# il-serbatoio.net
KiCad netlist of a schematic drawn in EAGLE
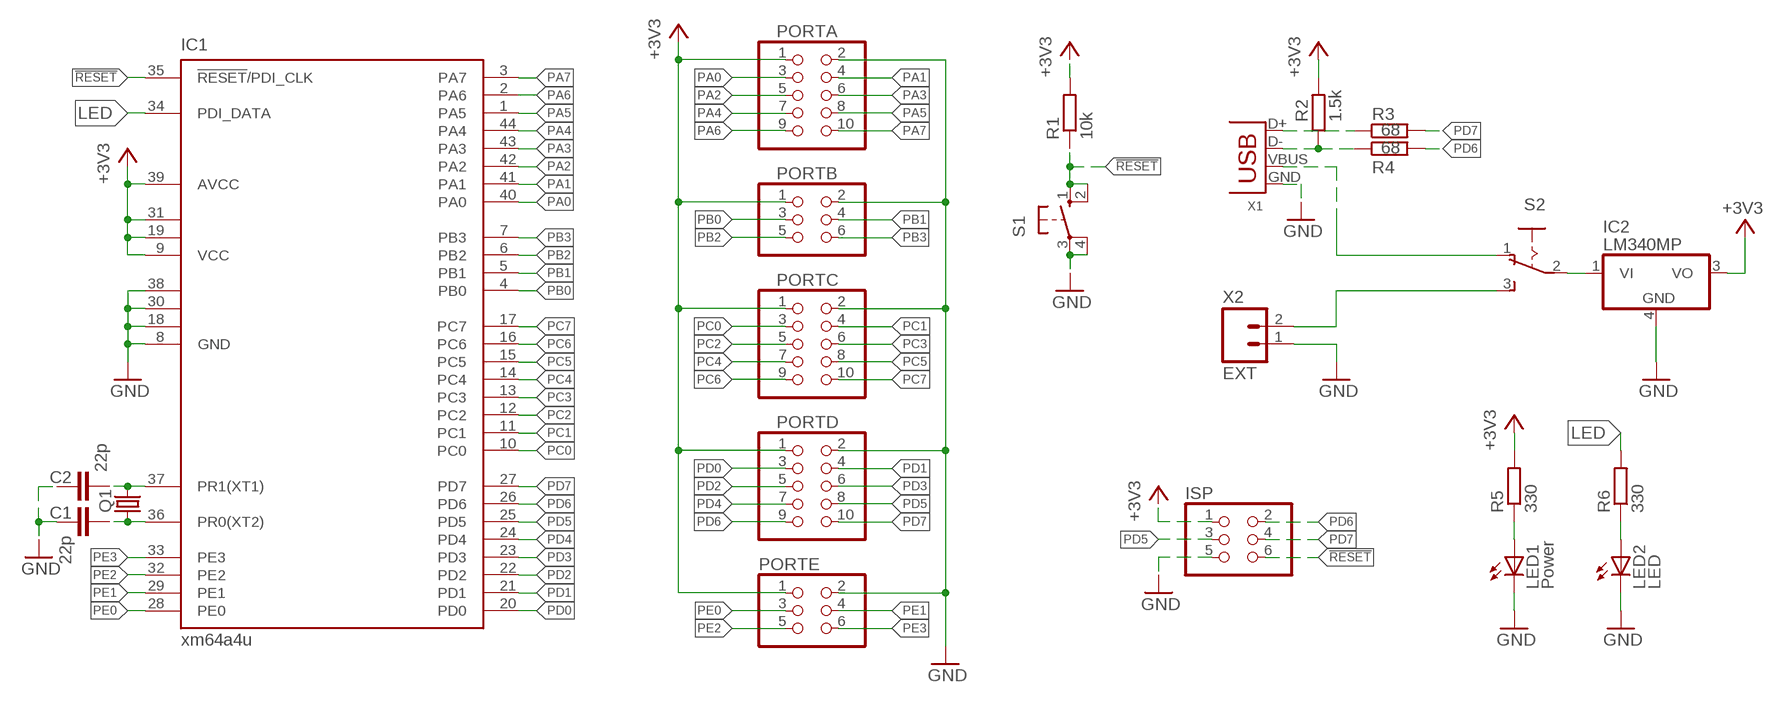
[diagram p0: schematic, sheet 1]

(export (version "E")
  (design (tool "Eeschema 10.0.6"))
  (components
    (comp (ref "C1")
      (value "22p")
      (footprint "eagle-import:C025-024X044")
      (libsource (lib "eagle-import") (part "C-EU025-024X044"))
    )
    (comp (ref "C2")
      (value "22p")
      (footprint "eagle-import:C025-024X044")
      (libsource (lib "eagle-import") (part "C-EU025-024X044"))
    )
    (comp (ref "IC1")
      (value "xm64a4u")
      (footprint "eagle-import:TQFP44")
      (libsource (lib "eagle-import") (part "XMEGA16A4A"))
    )
    (comp (ref "IC2")
      (value "LM340MP")
      (footprint "eagle-import:SOT223")
      (libsource (lib "eagle-import") (part "LM340?-MP05"))
    )
    (comp (ref "ISP")
      (value "PINHD-2X3")
      (footprint "eagle-import:2X03")
      (libsource (lib "eagle-import") (part "PINHD-2X3"))
    )
    (comp (ref "LED1")
      (value "Power")
      (footprint "eagle-import:CHIP-LED0805")
      (libsource (lib "eagle-import") (part "LEDCHIP-LED0805"))
    )
    (comp (ref "LED2")
      (value "LED")
      (footprint "eagle-import:CHIP-LED0805")
      (libsource (lib "eagle-import") (part "LEDCHIP-LED0805"))
    )
    (comp (ref "PORTA")
      (value "PINHD-2X5")
      (footprint "eagle-import:2X05")
      (libsource (lib "eagle-import") (part "PINHD-2X5"))
    )
    (comp (ref "PORTB")
      (value "PINHD-2X3")
      (footprint "eagle-import:2X03")
      (libsource (lib "eagle-import") (part "PINHD-2X3"))
    )
    (comp (ref "PORTC")
      (value "PINHD-2X5")
      (footprint "eagle-import:2X05")
      (libsource (lib "eagle-import") (part "PINHD-2X5"))
    )
    (comp (ref "PORTD")
      (value "PINHD-2X5")
      (footprint "eagle-import:2X05")
      (libsource (lib "eagle-import") (part "PINHD-2X5"))
    )
    (comp (ref "PORTE")
      (value "PINHD-2X3")
      (footprint "eagle-import:2X03")
      (libsource (lib "eagle-import") (part "PINHD-2X3"))
    )
    (comp (ref "Q1")
      (value "CRYSTALCTS406")
      (footprint "eagle-import:CTS406")
      (libsource (lib "eagle-import") (part "CRYSTALCTS406"))
    )
    (comp (ref "R1")
      (value "10k")
      (footprint "eagle-import:M0805")
      (libsource (lib "eagle-import") (part "R-EU_M0805"))
    )
    (comp (ref "R2")
      (value "1.5k")
      (footprint "eagle-import:M0805")
      (libsource (lib "eagle-import") (part "R-EU_M0805"))
    )
    (comp (ref "R3")
      (value "68")
      (footprint "eagle-import:M0805")
      (libsource (lib "eagle-import") (part "R-EU_M0805"))
    )
    (comp (ref "R4")
      (value "68")
      (footprint "eagle-import:M0805")
      (libsource (lib "eagle-import") (part "R-EU_M0805"))
    )
    (comp (ref "R5")
      (value "330")
      (footprint "eagle-import:M0805")
      (libsource (lib "eagle-import") (part "R-EU_M0805"))
    )
    (comp (ref "R6")
      (value "330")
      (footprint "eagle-import:M0805")
      (libsource (lib "eagle-import") (part "R-EU_M0805"))
    )
    (comp (ref "S1")
      (value "10-XX")
      (footprint "eagle-import:B3F-10XX")
      (fields (field (name "MPN") "B3F-1000"))
      (libsource (lib "eagle-import") (part "10-XX"))
    )
    (comp (ref "S2")
      (value "255SB")
      (footprint "eagle-import:255SB")
      (libsource (lib "eagle-import") (part "255SB"))
    )
    (comp (ref "X1")
      (value "USB-MB-S")
      (footprint "eagle-import:USB-MB-S")
      (libsource (lib "eagle-import") (part "USB-MB-S"))
    )
    (comp (ref "X2")
      (value "EXT")
      (footprint "eagle-import:JST-2-2MM-PTH-VERT-LOCK")
      (libsource (lib "eagle-import") (part "JST-22MM-PTH-VERT-LOCK"))
    )
  )
  (nets
    (net (code "1") (name "+3V3") (class "Default")
      (node (ref "IC1") (pin "19") (pinfunction "VCC1_19") (pintype "power_in"))
      (node (ref "IC1") (pin "31") (pinfunction "VCC2_31") (pintype "power_in"))
      (node (ref "IC1") (pin "39") (pinfunction "AVCC_39") (pintype "power_in"))
      (node (ref "IC1") (pin "9") (pinfunction "VCC_9") (pintype "power_in"))
      (node (ref "IC2") (pin "3") (pinfunction "VO_3") (pintype "passive"))
      (node (ref "ISP") (pin "1") (pinfunction "1_1") (pintype "passive"))
      (node (ref "PORTA") (pin "1") (pinfunction "1_1") (pintype "passive"))
      (node (ref "PORTB") (pin "1") (pinfunction "1_1") (pintype "passive"))
      (node (ref "PORTC") (pin "1") (pinfunction "1_1") (pintype "passive"))
      (node (ref "PORTD") (pin "1") (pinfunction "1_1") (pintype "passive"))
      (node (ref "PORTE") (pin "1") (pinfunction "1_1") (pintype "passive"))
      (node (ref "R1") (pin "2") (pinfunction "2_2") (pintype "passive"))
      (node (ref "R2") (pin "2") (pinfunction "2_2") (pintype "passive"))
      (node (ref "R5") (pin "2") (pinfunction "2_2") (pintype "passive"))
    )
    (net (code "2") (name "/~{RESET}") (class "Default")
      (node (ref "IC1") (pin "35") (pinfunction "~{RESET}/PDI_CLK_35") (pintype "bidirectional"))
      (node (ref "ISP") (pin "6") (pinfunction "6_6") (pintype "passive"))
      (node (ref "R1") (pin "1") (pinfunction "1_1") (pintype "passive"))
      (node (ref "S1") (pin "1") (pinfunction "S_1") (pintype "passive"))
      (node (ref "S1") (pin "2") (pinfunction "S1_2") (pintype "passive"))
    )
    (net (code "3") (name "GND") (class "Default")
      (node (ref "C1") (pin "1") (pinfunction "1_1") (pintype "passive"))
      (node (ref "C2") (pin "1") (pinfunction "1_1") (pintype "passive"))
      (node (ref "IC1") (pin "18") (pinfunction "GND1_18") (pintype "power_in"))
      (node (ref "IC1") (pin "30") (pinfunction "GND2_30") (pintype "power_in"))
      (node (ref "IC1") (pin "38") (pinfunction "GND3_38") (pintype "power_in"))
      (node (ref "IC1") (pin "8") (pinfunction "GND_8") (pintype "power_in"))
      (node (ref "IC2") (pin "4") (pinfunction "GND_4") (pintype "passive"))
      (node (ref "ISP") (pin "5") (pinfunction "5_5") (pintype "passive"))
      (node (ref "LED1") (pin "C") (pinfunction "C_C") (pintype "passive"))
      (node (ref "LED2") (pin "C") (pinfunction "C_C") (pintype "passive"))
      (node (ref "PORTA") (pin "2") (pinfunction "2_2") (pintype "passive"))
      (node (ref "PORTB") (pin "2") (pinfunction "2_2") (pintype "passive"))
      (node (ref "PORTC") (pin "2") (pinfunction "2_2") (pintype "passive"))
      (node (ref "PORTD") (pin "2") (pinfunction "2_2") (pintype "passive"))
      (node (ref "PORTE") (pin "2") (pinfunction "2_2") (pintype "passive"))
      (node (ref "S1") (pin "3") (pinfunction "P_3") (pintype "passive"))
      (node (ref "S1") (pin "4") (pinfunction "P1_4") (pintype "passive"))
      (node (ref "X1") (pin "GND") (pinfunction "GND_GND") (pintype "bidirectional"))
      (node (ref "X2") (pin "1") (pinfunction "1_1") (pintype "passive"))
    )
    (net (code "4") (name "LED") (class "Default")
      (node (ref "IC1") (pin "34") (pinfunction "PDI_DATA_34") (pintype "bidirectional"))
      (node (ref "R6") (pin "2") (pinfunction "2_2") (pintype "passive"))
    )
    (net (code "5") (name "Net-(IC1-PR0(XT2))") (class "Default")
      (node (ref "C1") (pin "2") (pinfunction "2_2") (pintype "passive"))
      (node (ref "IC1") (pin "36") (pinfunction "PR0(XT2)_36") (pintype "bidirectional"))
      (node (ref "Q1") (pin "1") (pinfunction "1_1") (pintype "passive"))
    )
    (net (code "6") (name "Net-(IC1-PR1(XT1))") (class "Default")
      (node (ref "C2") (pin "2") (pinfunction "2_2") (pintype "passive"))
      (node (ref "IC1") (pin "37") (pinfunction "PR1(XT1)_37") (pintype "bidirectional"))
      (node (ref "Q1") (pin "3") (pinfunction "2_3") (pintype "passive"))
    )
    (net (code "7") (name "Net-(IC2-VI)") (class "Default")
      (node (ref "IC2") (pin "1") (pinfunction "VI_1") (pintype "input"))
      (node (ref "S2") (pin "2") (pinfunction "P_2") (pintype "passive"))
    )
    (net (code "8") (name "Net-(LED1-PadA)") (class "Default")
      (node (ref "LED1") (pin "A") (pinfunction "A_A") (pintype "passive"))
      (node (ref "R5") (pin "1") (pinfunction "1_1") (pintype "passive"))
    )
    (net (code "9") (name "Net-(LED2-PadA)") (class "Default")
      (node (ref "LED2") (pin "A") (pinfunction "A_A") (pintype "passive"))
      (node (ref "R6") (pin "1") (pinfunction "1_1") (pintype "passive"))
    )
    (net (code "10") (name "Net-(R2-Pad1)") (class "Default")
      (node (ref "R2") (pin "1") (pinfunction "1_1") (pintype "passive"))
      (node (ref "R4") (pin "1") (pinfunction "1_1") (pintype "passive"))
      (node (ref "X1") (pin "D-") (pinfunction "D-_D-") (pintype "bidirectional"))
    )
    (net (code "11") (name "Net-(R3-Pad1)") (class "Default")
      (node (ref "R3") (pin "1") (pinfunction "1_1") (pintype "passive"))
      (node (ref "X1") (pin "D+") (pinfunction "D+_D+") (pintype "bidirectional"))
    )
    (net (code "12") (name "Net-(S2-O)") (class "Default")
      (node (ref "S2") (pin "1") (pinfunction "O_1") (pintype "passive"))
      (node (ref "X1") (pin "VBUS") (pinfunction "VBUS_VBUS") (pintype "bidirectional"))
    )
    (net (code "13") (name "Net-(S2-S)") (class "Default")
      (node (ref "S2") (pin "3") (pinfunction "S_3") (pintype "passive"))
      (node (ref "X2") (pin "2") (pinfunction "2_2") (pintype "passive"))
    )
    (net (code "14") (name "PA0") (class "Default")
      (node (ref "IC1") (pin "40") (pinfunction "PA0_40") (pintype "bidirectional"))
      (node (ref "PORTA") (pin "3") (pinfunction "3_3") (pintype "passive"))
    )
    (net (code "15") (name "PA1") (class "Default")
      (node (ref "IC1") (pin "41") (pinfunction "PA1_41") (pintype "bidirectional"))
      (node (ref "PORTA") (pin "4") (pinfunction "4_4") (pintype "passive"))
    )
    (net (code "16") (name "PA2") (class "Default")
      (node (ref "IC1") (pin "42") (pinfunction "PA2_42") (pintype "bidirectional"))
      (node (ref "PORTA") (pin "5") (pinfunction "5_5") (pintype "passive"))
    )
    (net (code "17") (name "PA3") (class "Default")
      (node (ref "IC1") (pin "43") (pinfunction "PA3_43") (pintype "bidirectional"))
      (node (ref "PORTA") (pin "6") (pinfunction "6_6") (pintype "passive"))
    )
    (net (code "18") (name "PA4") (class "Default")
      (node (ref "IC1") (pin "44") (pinfunction "PA4_44") (pintype "bidirectional"))
      (node (ref "PORTA") (pin "7") (pinfunction "7_7") (pintype "passive"))
    )
    (net (code "19") (name "PA5") (class "Default")
      (node (ref "IC1") (pin "1") (pinfunction "PA5_1") (pintype "bidirectional"))
      (node (ref "PORTA") (pin "8") (pinfunction "8_8") (pintype "passive"))
    )
    (net (code "20") (name "PA6") (class "Default")
      (node (ref "IC1") (pin "2") (pinfunction "PA6_2") (pintype "bidirectional"))
      (node (ref "PORTA") (pin "9") (pinfunction "9_9") (pintype "passive"))
    )
    (net (code "21") (name "PA7") (class "Default")
      (node (ref "IC1") (pin "3") (pinfunction "PA7_3") (pintype "bidirectional"))
      (node (ref "PORTA") (pin "10") (pinfunction "10_10") (pintype "passive"))
    )
    (net (code "22") (name "PB0") (class "Default")
      (node (ref "IC1") (pin "4") (pinfunction "PB0_4") (pintype "bidirectional"))
      (node (ref "PORTB") (pin "3") (pinfunction "3_3") (pintype "passive"))
    )
    (net (code "23") (name "PB1") (class "Default")
      (node (ref "IC1") (pin "5") (pinfunction "PB1_5") (pintype "bidirectional"))
      (node (ref "PORTB") (pin "4") (pinfunction "4_4") (pintype "passive"))
    )
    (net (code "24") (name "PB2") (class "Default")
      (node (ref "IC1") (pin "6") (pinfunction "PB2_6") (pintype "bidirectional"))
      (node (ref "PORTB") (pin "5") (pinfunction "5_5") (pintype "passive"))
    )
    (net (code "25") (name "PB3") (class "Default")
      (node (ref "IC1") (pin "7") (pinfunction "PB3_7") (pintype "bidirectional"))
      (node (ref "PORTB") (pin "6") (pinfunction "6_6") (pintype "passive"))
    )
    (net (code "26") (name "PC0") (class "Default")
      (node (ref "IC1") (pin "10") (pinfunction "PC0_10") (pintype "bidirectional"))
      (node (ref "PORTC") (pin "3") (pinfunction "3_3") (pintype "passive"))
    )
    (net (code "27") (name "PC1") (class "Default")
      (node (ref "IC1") (pin "11") (pinfunction "PC1_11") (pintype "bidirectional"))
      (node (ref "PORTC") (pin "4") (pinfunction "4_4") (pintype "passive"))
    )
    (net (code "28") (name "PC2") (class "Default")
      (node (ref "IC1") (pin "12") (pinfunction "PC2_12") (pintype "bidirectional"))
      (node (ref "PORTC") (pin "5") (pinfunction "5_5") (pintype "passive"))
    )
    (net (code "29") (name "PC3") (class "Default")
      (node (ref "IC1") (pin "13") (pinfunction "PC3_13") (pintype "bidirectional"))
      (node (ref "PORTC") (pin "6") (pinfunction "6_6") (pintype "passive"))
    )
    (net (code "30") (name "PC4") (class "Default")
      (node (ref "IC1") (pin "14") (pinfunction "PC4_14") (pintype "bidirectional"))
      (node (ref "PORTC") (pin "7") (pinfunction "7_7") (pintype "passive"))
    )
    (net (code "31") (name "PC5") (class "Default")
      (node (ref "IC1") (pin "15") (pinfunction "PC5_15") (pintype "bidirectional"))
      (node (ref "PORTC") (pin "8") (pinfunction "8_8") (pintype "passive"))
    )
    (net (code "32") (name "PC6") (class "Default")
      (node (ref "IC1") (pin "16") (pinfunction "PC6_16") (pintype "bidirectional"))
      (node (ref "PORTC") (pin "9") (pinfunction "9_9") (pintype "passive"))
    )
    (net (code "33") (name "PC7") (class "Default")
      (node (ref "IC1") (pin "17") (pinfunction "PC7_17") (pintype "bidirectional"))
      (node (ref "PORTC") (pin "10") (pinfunction "10_10") (pintype "passive"))
    )
    (net (code "34") (name "PD0") (class "Default")
      (node (ref "IC1") (pin "20") (pinfunction "PD0_20") (pintype "bidirectional"))
      (node (ref "PORTD") (pin "3") (pinfunction "3_3") (pintype "passive"))
    )
    (net (code "35") (name "PD1") (class "Default")
      (node (ref "IC1") (pin "21") (pinfunction "PD1_21") (pintype "bidirectional"))
      (node (ref "PORTD") (pin "4") (pinfunction "4_4") (pintype "passive"))
    )
    (net (code "36") (name "PD2") (class "Default")
      (node (ref "IC1") (pin "22") (pinfunction "PD2_22") (pintype "bidirectional"))
      (node (ref "PORTD") (pin "5") (pinfunction "5_5") (pintype "passive"))
    )
    (net (code "37") (name "PD3") (class "Default")
      (node (ref "IC1") (pin "23") (pinfunction "PD3_23") (pintype "bidirectional"))
      (node (ref "PORTD") (pin "6") (pinfunction "6_6") (pintype "passive"))
    )
    (net (code "38") (name "PD4") (class "Default")
      (node (ref "IC1") (pin "24") (pinfunction "PD4_24") (pintype "bidirectional"))
      (node (ref "PORTD") (pin "7") (pinfunction "7_7") (pintype "passive"))
    )
    (net (code "39") (name "PD5") (class "Default")
      (node (ref "IC1") (pin "25") (pinfunction "PD5_25") (pintype "bidirectional"))
      (node (ref "ISP") (pin "3") (pinfunction "3_3") (pintype "passive"))
      (node (ref "PORTD") (pin "8") (pinfunction "8_8") (pintype "passive"))
    )
    (net (code "40") (name "PD6") (class "Default")
      (node (ref "IC1") (pin "26") (pinfunction "PD6_26") (pintype "bidirectional"))
      (node (ref "ISP") (pin "2") (pinfunction "2_2") (pintype "passive"))
      (node (ref "PORTD") (pin "9") (pinfunction "9_9") (pintype "passive"))
      (node (ref "R4") (pin "2") (pinfunction "2_2") (pintype "passive"))
    )
    (net (code "41") (name "PD7") (class "Default")
      (node (ref "IC1") (pin "27") (pinfunction "PD7_27") (pintype "bidirectional"))
      (node (ref "ISP") (pin "4") (pinfunction "4_4") (pintype "passive"))
      (node (ref "PORTD") (pin "10") (pinfunction "10_10") (pintype "passive"))
      (node (ref "R3") (pin "2") (pinfunction "2_2") (pintype "passive"))
    )
    (net (code "42") (name "PE0") (class "Default")
      (node (ref "IC1") (pin "28") (pinfunction "PE0_28") (pintype "bidirectional"))
      (node (ref "PORTE") (pin "3") (pinfunction "3_3") (pintype "passive"))
    )
    (net (code "43") (name "PE1") (class "Default")
      (node (ref "IC1") (pin "29") (pinfunction "PE1_29") (pintype "bidirectional"))
      (node (ref "PORTE") (pin "4") (pinfunction "4_4") (pintype "passive"))
    )
    (net (code "44") (name "PE2") (class "Default")
      (node (ref "IC1") (pin "32") (pinfunction "PE2_32") (pintype "bidirectional"))
      (node (ref "PORTE") (pin "5") (pinfunction "5_5") (pintype "passive"))
    )
    (net (code "45") (name "PE3") (class "Default")
      (node (ref "IC1") (pin "33") (pinfunction "PE3_33") (pintype "bidirectional"))
      (node (ref "PORTE") (pin "6") (pinfunction "6_6") (pintype "passive"))
    )
  )
)
